# SourceOptode.net
KiCad netlist of a schematic drawn in Altium Designer
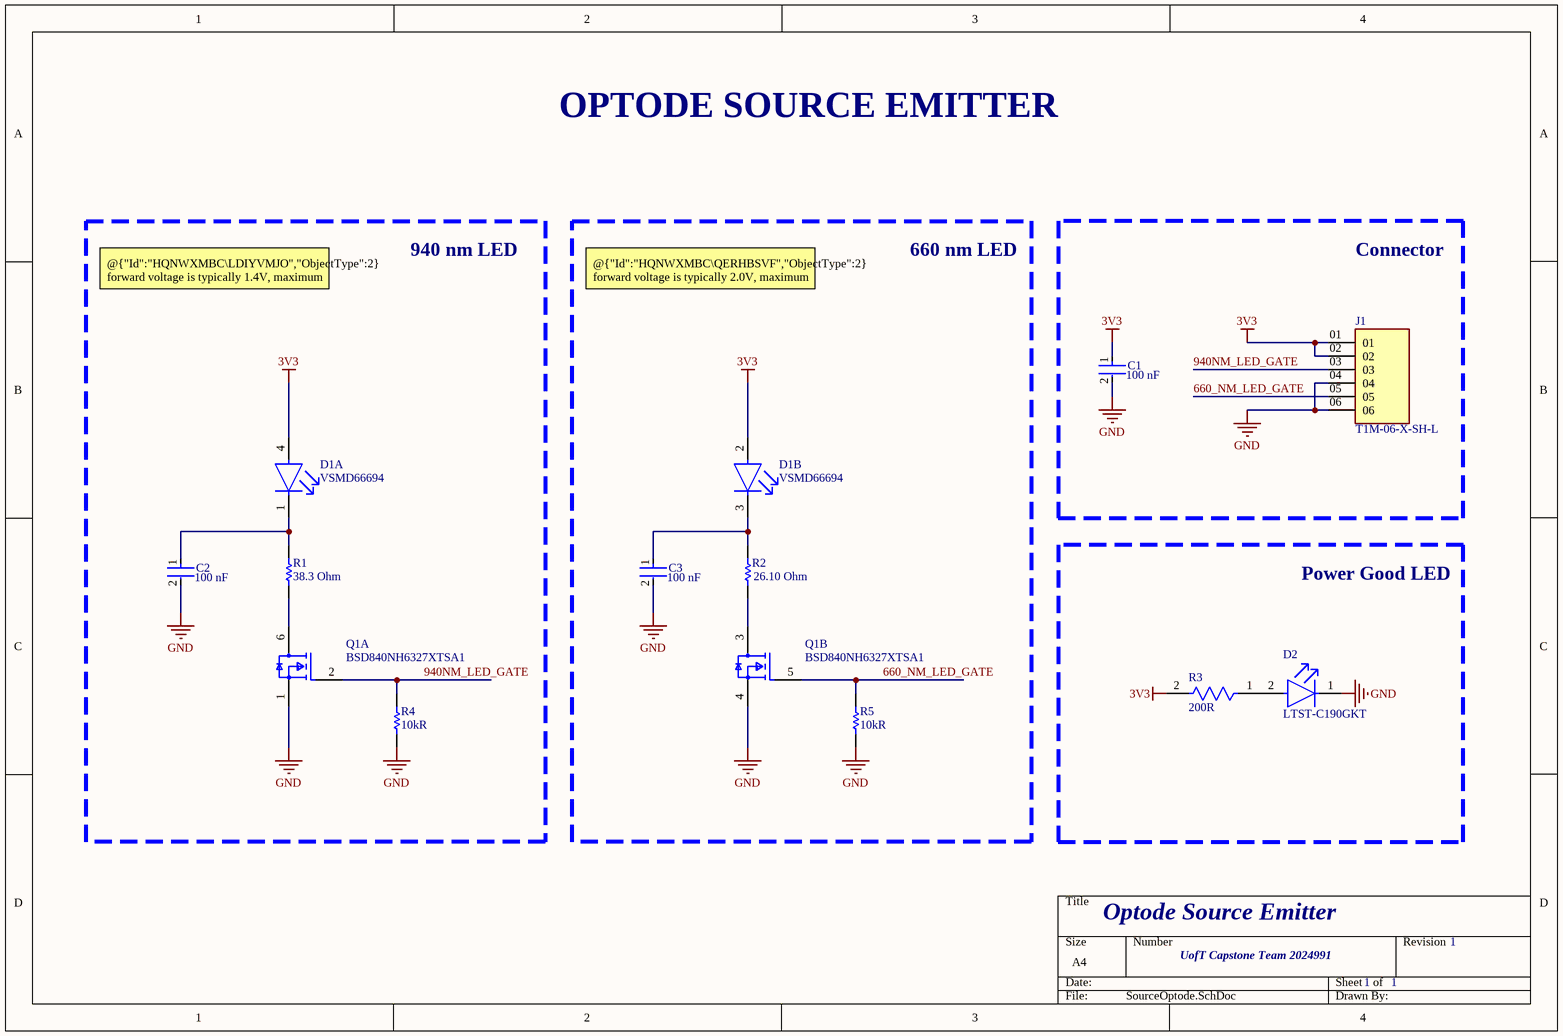
[diagram p0: SourceOptode.SchDoc]

(export (version "E")
  (design (tool "Eeschema 10.0.6"))
  (components
    (comp (ref "C1")
      (value "CC0603KRX7R7BB104")
      (footprint "FP-CC0603-DA-MFG")
      (description "CAP CER 0.1UF 16V X7R 0603")
      (fields
        (field (name "OCTOPART") "https://octopart.com/cc0603krx7r7bb104-yageo-192941")
        (field (name "TOLERANCE") "0.1")
        (field (name "CAPACITANCE") "100 nF")
      )
      (libsource (lib "Altium Content Vault") (part "11868f565c42a9108669ba33697ecf6"))
    )
    (comp (ref "C2")
      (value "CC0603KRX7R7BB104")
      (footprint "FP-CC0603-DA-MFG")
      (description "CAP CER 0.1UF 16V X7R 0603")
      (fields
        (field (name "OCTOPART") "https://octopart.com/cc0603krx7r7bb104-yageo-192941")
        (field (name "TOLERANCE") "0.1")
        (field (name "CAPACITANCE") "100 nF")
      )
      (libsource (lib "Altium Content Vault") (part "11868f565c42a9108669ba33697ecf6"))
    )
    (comp (ref "C3")
      (value "CC0603KRX7R7BB104")
      (footprint "FP-CC0603-DA-MFG")
      (description "CAP CER 0.1UF 16V X7R 0603")
      (fields
        (field (name "OCTOPART") "https://octopart.com/cc0603krx7r7bb104-yageo-192941")
        (field (name "TOLERANCE") "0.1")
        (field (name "CAPACITANCE") "100 nF")
      )
      (libsource (lib "Altium Content Vault") (part "11868f565c42a9108669ba33697ecf6"))
    )
    (comp (ref "D1")
      (value "VSMD66694")
      (footprint "FP-6_550-5347_01-4-MFG")
      (description "EMITTER DUAL 660/940NM SQURE PCB")
      (fields
        (field (name "MANUFACTURER") "Vishay Semiconductor Opto Division")
        (field (name "OCTOPART") "https://octopart.com/vsmd66694-vishay-74221794")
      )
      (libsource (lib "Altium Content Vault") (part "f63fdef09506549d47f9c99805bef80"))
    )
    (comp (ref "D2")
      (value "LTST-C190GKT")
      (footprint "FP-LTST-C190GKT-MFG")
      (description "LED GREEN CLEAR CHIP SMD")
      (fields (field (name "VOLTAGE") "2V"))
      (libsource (lib "Altium Content Vault") (part "8706943c75ba83719d021d2fdc84c58"))
    )
    (comp (ref "J1")
      (value "T1M-06-X-SH-L")
      (footprint "SAMTEC_T1M-06-X-SH-L")
      (description "Connector Header Surface Mount, Right Angle 6 position 0.039\" (1.00mm)")
      (fields (field (name "MF") "Samtec"))
      (libsource (lib "SourceOptode") (part "T1M-06-X-SH-L"))
    )
    (comp (ref "Q1")
      (value "BSD840NH6327XTSA1")
      (footprint "FP-PG-SOT363-6-MFG")
      (description "MOSFET 2N-CH 20V 0.88A SOT363")
      (libsource (lib "Altium Content Vault") (part "6559164231102c4ec4f565336d3f230"))
    )
    (comp (ref "R1")
      (value "RK73H1JTTD38R3F")
      (footprint "RESC1608X55X30LL20T10")
      (fields (field (name "MANUFACTURER") "KOA Speer") (field (name "RESISTANCE") "38.3 Ohm"))
      (libsource (lib "Altium Content Vault") (part "RES"))
    )
    (comp (ref "R2")
      (value "26.10 Ohm")
      (footprint "RESC0603(1608)_L")
      (description "26R1 0.1W 1% 0603 (1608 Metric)  SMD")
      (fields (field (name "POWER") "0.1 W") (field (name "TOLERANCE") "1 %"))
      (libsource (lib "Altium Content Vault") (part "RES"))
    )
    (comp (ref "R3")
      (value "CRCW0603200RFKEA")
      (footprint "FP-CRCW0603-e3-MFG")
      (description "RES Thick Film, 200Ω, 1%, 0.1W, 100ppm/°C, 0603")
      (fields (field (name "TOLERANCE") "1%") (field (name "RESISTANCE") "200R"))
      (libsource (lib "Altium Content Vault") (part "1029c3af85768c4190bb7ad29bc67b5"))
    )
    (comp (ref "R4")
      (value "CRCW060310K0FKEA")
      (footprint "RESC1609X50X30NL8T20")
      (description "Chip Resistor, 10 KOhm, +/- 1%, 100 mW, -55 to 155 degC, 0603 (1608 Metric), RoHS, Tape and Reel")
      (fields (field (name "MANUFACTURER") "Vishay Semiconductor") (field (name "RESISTANCE") "10kR"))
      (libsource (lib "Altium Content Vault") (part "RES-2"))
    )
    (comp (ref "R5")
      (value "CRCW060310K0FKEA")
      (footprint "RESC1609X50X30NL8T20")
      (description "Chip Resistor, 10 KOhm, +/- 1%, 100 mW, -55 to 155 degC, 0603 (1608 Metric), RoHS, Tape and Reel")
      (fields (field (name "MANUFACTURER") "Vishay Semiconductor") (field (name "RESISTANCE") "10kR"))
      (libsource (lib "Altium Content Vault") (part "RES-2"))
    )
  )
  (nets
    (net (code "1") (name "/660_NM_LED_GATE") (class "Default")
      (node (ref "J1") (pin "05") (pinfunction "05_05") (pintype "passive"))
      (node (ref "Q1") (pin "5") (pinfunction "2_GATE_5") (pintype "passive"))
      (node (ref "R5") (pin "2") (pinfunction "2_2") (pintype "passive"))
    )
    (net (code "2") (name "/940NM_LED_GATE") (class "Default")
      (node (ref "J1") (pin "03") (pinfunction "03_03") (pintype "passive"))
      (node (ref "Q1") (pin "2") (pinfunction "1_GATE_2") (pintype "passive"))
      (node (ref "R4") (pin "2") (pinfunction "2_2") (pintype "passive"))
    )
    (net (code "3") (name "3V3") (class "Default")
      (node (ref "C1") (pin "1") (pinfunction "1_1") (pintype "passive"))
      (node (ref "D1") (pin "2") (pinfunction "RED_A_2") (pintype "passive"))
      (node (ref "D1") (pin "4") (pinfunction "IR_anode_4") (pintype "passive"))
      (node (ref "J1") (pin "01") (pinfunction "01_01") (pintype "passive"))
      (node (ref "J1") (pin "02") (pinfunction "02_02") (pintype "passive"))
      (node (ref "R3") (pin "2") (pinfunction "2_2") (pintype "passive"))
    )
    (net (code "4") (name "GND") (class "Default")
      (node (ref "C1") (pin "2") (pinfunction "2_2") (pintype "passive"))
      (node (ref "C2") (pin "2") (pinfunction "2_2") (pintype "passive"))
      (node (ref "C3") (pin "2") (pinfunction "2_2") (pintype "passive"))
      (node (ref "D2") (pin "1") (pinfunction "C_1") (pintype "passive"))
      (node (ref "J1") (pin "04") (pinfunction "04_04") (pintype "passive"))
      (node (ref "J1") (pin "06") (pinfunction "06_06") (pintype "passive"))
      (node (ref "Q1") (pin "1") (pinfunction "1_SOURCE_1") (pintype "passive"))
      (node (ref "Q1") (pin "4") (pinfunction "2_SOURCE_4") (pintype "passive"))
      (node (ref "R4") (pin "1") (pinfunction "1_1") (pintype "passive"))
      (node (ref "R5") (pin "1") (pinfunction "1_1") (pintype "passive"))
    )
    (net (code "5") (name "Net-(D1A-IR_cathode)") (class "Default")
      (node (ref "C2") (pin "1") (pinfunction "1_1") (pintype "passive"))
      (node (ref "D1") (pin "1") (pinfunction "IR_cathode_1") (pintype "passive"))
      (node (ref "R1") (pin "2") (pinfunction "2_2") (pintype "passive"))
    )
    (net (code "6") (name "Net-(D1B-RED_C)") (class "Default")
      (node (ref "C3") (pin "1") (pinfunction "1_1") (pintype "passive"))
      (node (ref "D1") (pin "3") (pinfunction "RED_C_3") (pintype "passive"))
      (node (ref "R2") (pin "2") (pinfunction "2_2") (pintype "passive"))
    )
    (net (code "7") (name "Net-(D2-A)") (class "Default")
      (node (ref "D2") (pin "2") (pinfunction "A_2") (pintype "passive"))
      (node (ref "R3") (pin "1") (pinfunction "1_1") (pintype "passive"))
    )
    (net (code "8") (name "Net-(Q1A-1_DRAIN)") (class "Default")
      (node (ref "Q1") (pin "6") (pinfunction "1_DRAIN_6") (pintype "passive"))
      (node (ref "R1") (pin "1") (pinfunction "1_1") (pintype "passive"))
    )
    (net (code "9") (name "Net-(Q1B-2_DRAIN)") (class "Default")
      (node (ref "Q1") (pin "3") (pinfunction "2_DRAIN_3") (pintype "passive"))
      (node (ref "R2") (pin "1") (pinfunction "1_1") (pintype "passive"))
    )
  )
)
